# PMOD_Shifter_3v3_to_1v8.net
KiCad netlist of a schematic drawn in Altium Designer
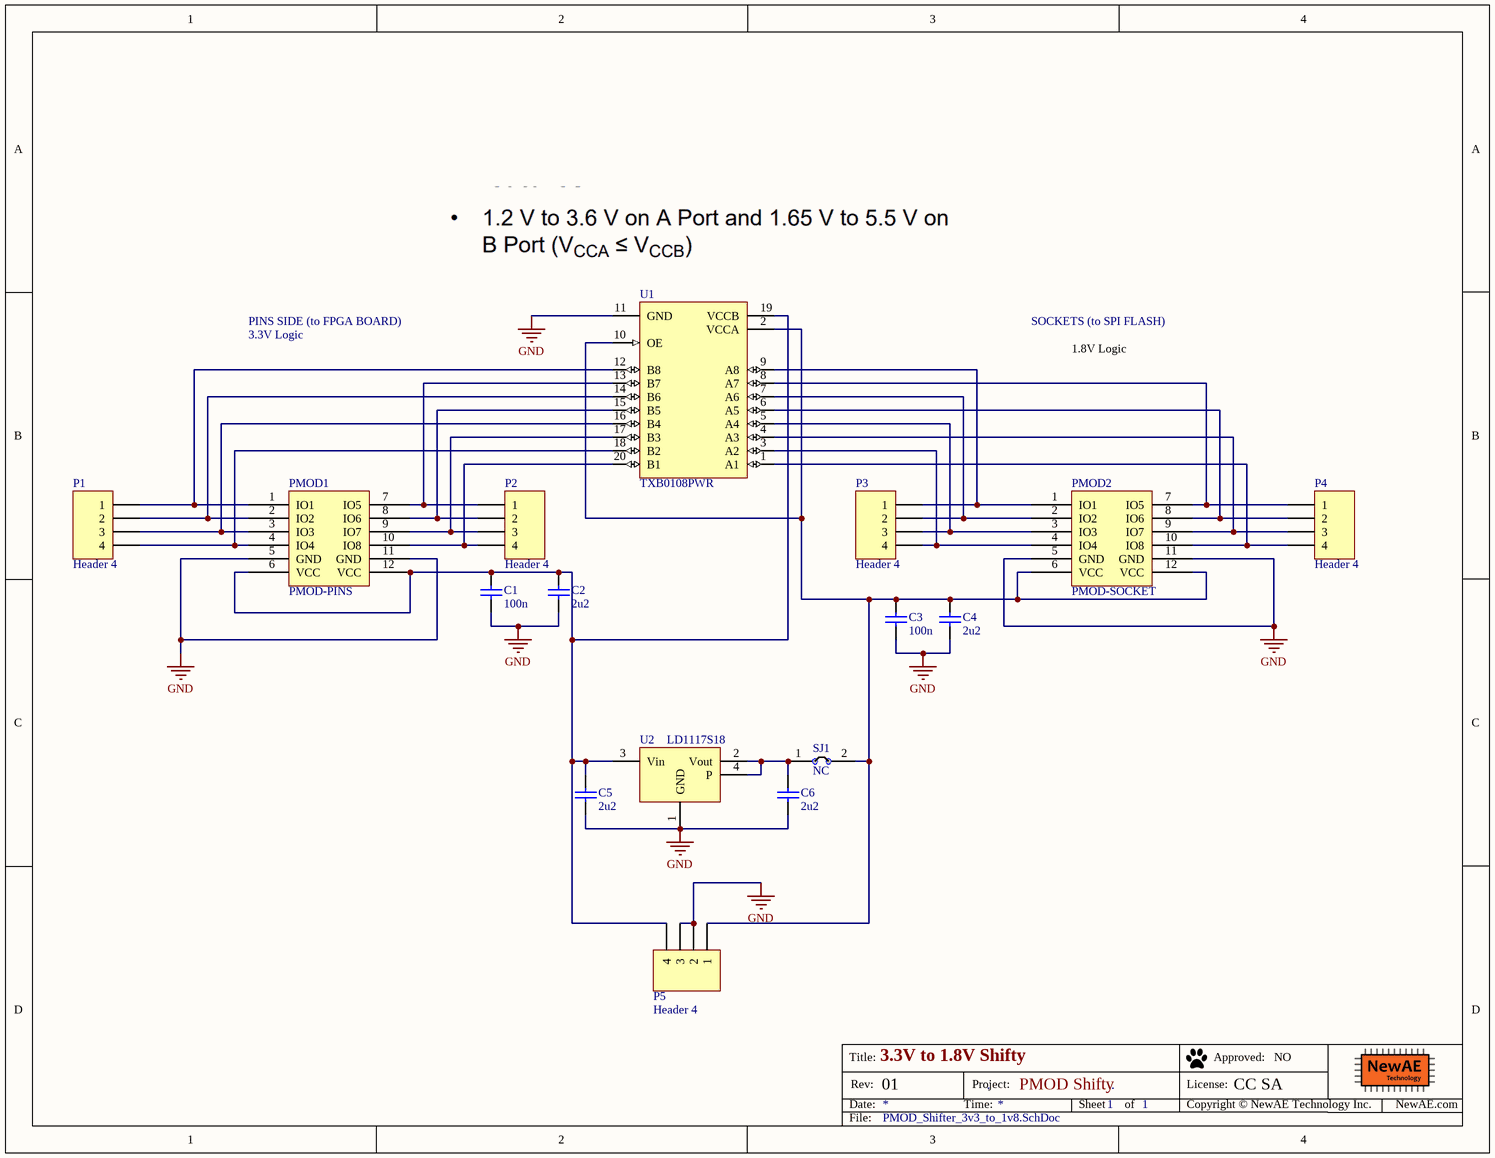
[diagram p0: PMOD_Shifter_3v3_to_1v8.SchDoc]

(export (version "E")
  (design (tool "Eeschema 10.0.6"))
  (components
    (comp (ref "C1")
      (value "100n")
      (footprint "CAPC0603_M")
      (description "100n, 0603")
      (fields (field (name "PART NUMBER") "CCHIP-100n-0603"))
      (libsource (lib "NewAE_AltiumLib") (part "CAP"))
    )
    (comp (ref "C2")
      (value "2u2")
      (footprint "CAPC0603_M")
      (description "2u2, 0603")
      (fields (field (name "PART NUMBER") "CCHIP-2u2-0603"))
      (libsource (lib "NewAE_AltiumLib") (part "CAP"))
    )
    (comp (ref "C3")
      (value "100n")
      (footprint "CAPC0603_M")
      (description "100n, 0603")
      (fields (field (name "PART NUMBER") "CCHIP-100n-0603"))
      (libsource (lib "NewAE_AltiumLib") (part "CAP"))
    )
    (comp (ref "C4")
      (value "2u2")
      (footprint "CAPC0603_M")
      (description "2u2, 0603")
      (fields (field (name "PART NUMBER") "CCHIP-2u2-0603"))
      (libsource (lib "NewAE_AltiumLib") (part "CAP"))
    )
    (comp (ref "C5")
      (value "2u2")
      (footprint "CAPC0603_M")
      (description "2u2, 0603")
      (fields (field (name "PART NUMBER") "CCHIP-2u2-0603"))
      (libsource (lib "NewAE_AltiumLib") (part "CAP"))
    )
    (comp (ref "C6")
      (value "2u2")
      (footprint "CAPC0603_M")
      (description "2u2, 0603")
      (fields (field (name "PART NUMBER") "CCHIP-2u2-0603"))
      (libsource (lib "NewAE_AltiumLib") (part "CAP"))
    )
    (comp (ref "P1")
      (value "Header 4")
      (footprint "HDR1X4")
      (description "Header, 4-Pin")
      (fields (field (name "PUBLISHER") "Altium Limited"))
      (libsource (lib "Miscellaneous Connectors") (part "Header 4"))
    )
    (comp (ref "P2")
      (value "Header 4")
      (footprint "HDR1X4")
      (description "Header, 4-Pin")
      (fields (field (name "PUBLISHER") "Altium Limited"))
      (libsource (lib "") (part "Header 4_1"))
    )
    (comp (ref "P3")
      (value "Header 4")
      (footprint "HDR1X4")
      (description "Header, 4-Pin")
      (fields (field (name "PUBLISHER") "Altium Limited"))
      (libsource (lib "Miscellaneous Connectors") (part "Header 4"))
    )
    (comp (ref "P4")
      (value "Header 4")
      (footprint "HDR1X4")
      (description "Header, 4-Pin")
      (fields (field (name "PUBLISHER") "Altium Limited"))
      (libsource (lib "") (part "Header 4_1"))
    )
    (comp (ref "P5")
      (value "Header 4")
      (footprint "HDR1X4")
      (description "Header, 4-Pin")
      (fields (field (name "PUBLISHER") "Altium Limited"))
      (libsource (lib "Miscellaneous Connectors") (part "Header 4"))
    )
    (comp (ref "PMOD1")
      (value "PMOD-PINS")
      (footprint "PMOD-68021-212HLF-MALE")
      (fields (field (name "PART NUMBER") "PMOD_2ROW_MALERATH"))
      (libsource (lib "NewAE_AltiumLib") (part "12PIN_RA_FEMALE"))
    )
    (comp (ref "PMOD2")
      (value "PMOD-SOCKET")
      (footprint "SAMTEC_SSW_106_02_X_D_RA_PMOD")
      (fields (field (name "PART NUMBER") "PMOD_2ROW_FEMALERATH"))
      (libsource (lib "NewAE_AltiumLib") (part "12PIN_RA_FEMALE"))
    )
    (comp (ref "SJ1")
      (value "NC")
      (footprint "SJ_2S_NC")
      (description "Solder Jumper, NC")
      (fields (field (name "PART NUMBER") "SJ_2S"))
      (libsource (lib "NewAE_AltiumLib") (part "SJ_2S"))
    )
    (comp (ref "U1")
      (value "TXB0108PWR")
      (footprint "PW0020A_L")
      (fields (field (name "MANUFACTURER") "Texas Instruments"))
      (libsource (lib "Altium Content Vault") (part "TI-TXB0108-PW-20"))
    )
    (comp (ref "U2")
      (value "LD1117S18")
      (footprint "SOT-223")
      (description "IC REG LIN POS 1.8V 800MA SOT223")
      (libsource (lib "NewAE_AltiumLib") (part "LD1117S33"))
    )
  )
  (nets
    (net (code "1") (name "GND") (class "Default")
      (node (ref "C1") (pin "2") (pinfunction "2_2") (pintype "passive"))
      (node (ref "C2") (pin "2") (pinfunction "2_2") (pintype "passive"))
      (node (ref "C3") (pin "2") (pinfunction "2_2") (pintype "passive"))
      (node (ref "C4") (pin "2") (pinfunction "2_2") (pintype "passive"))
      (node (ref "C5") (pin "2") (pinfunction "2_2") (pintype "passive"))
      (node (ref "C6") (pin "2") (pinfunction "2_2") (pintype "passive"))
      (node (ref "P5") (pin "2") (pinfunction "2_2") (pintype "passive"))
      (node (ref "P5") (pin "3") (pinfunction "3_3") (pintype "passive"))
      (node (ref "PMOD1") (pin "11") (pinfunction "GND_11") (pintype "passive"))
      (node (ref "PMOD1") (pin "5") (pinfunction "GND_5") (pintype "passive"))
      (node (ref "PMOD2") (pin "11") (pinfunction "GND_11") (pintype "passive"))
      (node (ref "PMOD2") (pin "5") (pinfunction "GND_5") (pintype "passive"))
      (node (ref "U1") (pin "11") (pinfunction "GND_11") (pintype "power_in"))
      (node (ref "U2") (pin "1") (pinfunction "GND_1") (pintype "passive"))
    )
    (net (code "2") (name "Net-(PMOD1-IO1)") (class "Default")
      (node (ref "P1") (pin "1") (pinfunction "1_1") (pintype "passive"))
      (node (ref "PMOD1") (pin "1") (pinfunction "IO1_1") (pintype "passive"))
      (node (ref "U1") (pin "12") (pinfunction "B8_12") (pintype "bidirectional"))
    )
    (net (code "3") (name "Net-(PMOD1-IO2)") (class "Default")
      (node (ref "P1") (pin "2") (pinfunction "2_2") (pintype "passive"))
      (node (ref "PMOD1") (pin "2") (pinfunction "IO2_2") (pintype "passive"))
      (node (ref "U1") (pin "14") (pinfunction "B6_14") (pintype "bidirectional"))
    )
    (net (code "4") (name "Net-(PMOD1-IO3)") (class "Default")
      (node (ref "P1") (pin "3") (pinfunction "3_3") (pintype "passive"))
      (node (ref "PMOD1") (pin "3") (pinfunction "IO3_3") (pintype "passive"))
      (node (ref "U1") (pin "16") (pinfunction "B4_16") (pintype "bidirectional"))
    )
    (net (code "5") (name "Net-(PMOD1-IO4)") (class "Default")
      (node (ref "P1") (pin "4") (pinfunction "4_4") (pintype "passive"))
      (node (ref "PMOD1") (pin "4") (pinfunction "IO4_4") (pintype "passive"))
      (node (ref "U1") (pin "18") (pinfunction "B2_18") (pintype "bidirectional"))
    )
    (net (code "6") (name "Net-(PMOD1-IO5)") (class "Default")
      (node (ref "P2") (pin "1") (pinfunction "1_1") (pintype "passive"))
      (node (ref "PMOD1") (pin "7") (pinfunction "IO5_7") (pintype "passive"))
      (node (ref "U1") (pin "13") (pinfunction "B7_13") (pintype "bidirectional"))
    )
    (net (code "7") (name "Net-(PMOD1-IO6)") (class "Default")
      (node (ref "P2") (pin "2") (pinfunction "2_2") (pintype "passive"))
      (node (ref "PMOD1") (pin "8") (pinfunction "IO6_8") (pintype "passive"))
      (node (ref "U1") (pin "15") (pinfunction "B5_15") (pintype "bidirectional"))
    )
    (net (code "8") (name "Net-(PMOD1-IO7)") (class "Default")
      (node (ref "P2") (pin "3") (pinfunction "3_3") (pintype "passive"))
      (node (ref "PMOD1") (pin "9") (pinfunction "IO7_9") (pintype "passive"))
      (node (ref "U1") (pin "17") (pinfunction "B3_17") (pintype "bidirectional"))
    )
    (net (code "9") (name "Net-(PMOD1-IO8)") (class "Default")
      (node (ref "P2") (pin "4") (pinfunction "4_4") (pintype "passive"))
      (node (ref "PMOD1") (pin "10") (pinfunction "IO8_10") (pintype "passive"))
      (node (ref "U1") (pin "20") (pinfunction "B1_20") (pintype "bidirectional"))
    )
    (net (code "10") (name "Net-(PMOD2-IO1)") (class "Default")
      (node (ref "P3") (pin "1") (pinfunction "1_1") (pintype "passive"))
      (node (ref "PMOD2") (pin "1") (pinfunction "IO1_1") (pintype "passive"))
      (node (ref "U1") (pin "9") (pinfunction "A8_9") (pintype "bidirectional"))
    )
    (net (code "11") (name "Net-(PMOD2-IO2)") (class "Default")
      (node (ref "P3") (pin "2") (pinfunction "2_2") (pintype "passive"))
      (node (ref "PMOD2") (pin "2") (pinfunction "IO2_2") (pintype "passive"))
      (node (ref "U1") (pin "7") (pinfunction "A6_7") (pintype "bidirectional"))
    )
    (net (code "12") (name "Net-(PMOD2-IO3)") (class "Default")
      (node (ref "P3") (pin "3") (pinfunction "3_3") (pintype "passive"))
      (node (ref "PMOD2") (pin "3") (pinfunction "IO3_3") (pintype "passive"))
      (node (ref "U1") (pin "5") (pinfunction "A4_5") (pintype "bidirectional"))
    )
    (net (code "13") (name "Net-(PMOD2-IO4)") (class "Default")
      (node (ref "P3") (pin "4") (pinfunction "4_4") (pintype "passive"))
      (node (ref "PMOD2") (pin "4") (pinfunction "IO4_4") (pintype "passive"))
      (node (ref "U1") (pin "3") (pinfunction "A2_3") (pintype "bidirectional"))
    )
    (net (code "14") (name "Net-(PMOD2-IO5)") (class "Default")
      (node (ref "P4") (pin "1") (pinfunction "1_1") (pintype "passive"))
      (node (ref "PMOD2") (pin "7") (pinfunction "IO5_7") (pintype "passive"))
      (node (ref "U1") (pin "8") (pinfunction "A7_8") (pintype "bidirectional"))
    )
    (net (code "15") (name "Net-(PMOD2-IO6)") (class "Default")
      (node (ref "P4") (pin "2") (pinfunction "2_2") (pintype "passive"))
      (node (ref "PMOD2") (pin "8") (pinfunction "IO6_8") (pintype "passive"))
      (node (ref "U1") (pin "6") (pinfunction "A5_6") (pintype "bidirectional"))
    )
    (net (code "16") (name "Net-(PMOD2-IO7)") (class "Default")
      (node (ref "P4") (pin "3") (pinfunction "3_3") (pintype "passive"))
      (node (ref "PMOD2") (pin "9") (pinfunction "IO7_9") (pintype "passive"))
      (node (ref "U1") (pin "4") (pinfunction "A3_4") (pintype "bidirectional"))
    )
    (net (code "17") (name "Net-(PMOD2-IO8)") (class "Default")
      (node (ref "P4") (pin "4") (pinfunction "4_4") (pintype "passive"))
      (node (ref "PMOD2") (pin "10") (pinfunction "IO8_10") (pintype "passive"))
      (node (ref "U1") (pin "1") (pinfunction "A1_1") (pintype "bidirectional"))
    )
    (net (code "18") (name "Net-(U1-OE)") (class "Default")
      (node (ref "C3") (pin "1") (pinfunction "1_1") (pintype "passive"))
      (node (ref "C4") (pin "1") (pinfunction "1_1") (pintype "passive"))
      (node (ref "P5") (pin "1") (pinfunction "1_1") (pintype "passive"))
      (node (ref "PMOD2") (pin "12") (pinfunction "VCC_12") (pintype "passive"))
      (node (ref "PMOD2") (pin "6") (pinfunction "VCC_6") (pintype "passive"))
      (node (ref "SJ1") (pin "2") (pinfunction "2_2") (pintype "passive"))
      (node (ref "U1") (pin "10") (pinfunction "OE_10") (pintype "input"))
      (node (ref "U1") (pin "2") (pinfunction "VCCA_2") (pintype "power_in"))
    )
    (net (code "19") (name "Net-(U1-VCCB)") (class "Default")
      (node (ref "C1") (pin "1") (pinfunction "1_1") (pintype "passive"))
      (node (ref "C2") (pin "1") (pinfunction "1_1") (pintype "passive"))
      (node (ref "C5") (pin "1") (pinfunction "1_1") (pintype "passive"))
      (node (ref "P5") (pin "4") (pinfunction "4_4") (pintype "passive"))
      (node (ref "PMOD1") (pin "12") (pinfunction "VCC_12") (pintype "passive"))
      (node (ref "PMOD1") (pin "6") (pinfunction "VCC_6") (pintype "passive"))
      (node (ref "U1") (pin "19") (pinfunction "VCCB_19") (pintype "power_in"))
      (node (ref "U2") (pin "3") (pinfunction "Vin_3") (pintype "passive"))
    )
    (net (code "20") (name "Net-(U2-P)") (class "Default")
      (node (ref "C6") (pin "1") (pinfunction "1_1") (pintype "passive"))
      (node (ref "SJ1") (pin "1") (pinfunction "1_1") (pintype "passive"))
      (node (ref "U2") (pin "2") (pinfunction "Vout_2") (pintype "passive"))
      (node (ref "U2") (pin "4") (pinfunction "P_4") (pintype "passive"))
    )
  )
)
